# mux_usb.net
KiCad netlist of a schematic drawn in Altium Designer
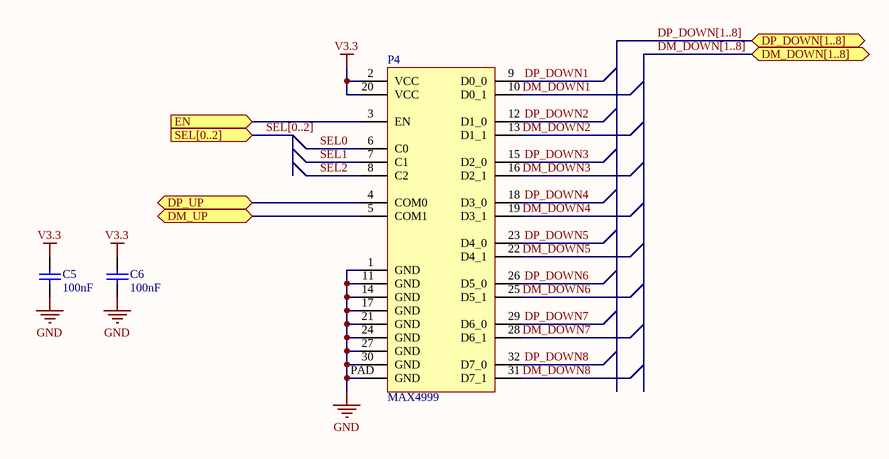
[diagram p0: mux_usb.SchDoc]

(export (version "E")
  (design (tool "Eeschema 10.0.6"))
  (components
    (comp (ref "C5") (value "100nF") (footprint "0402") (libsource (lib "misc") (part "Capacitor")))
    (comp (ref "C6") (value "100nF") (footprint "0402") (libsource (lib "misc") (part "Capacitor")))
    (comp (ref "P4") (value "MAX4999") (footprint "MAXIM_T3255+4") (libsource (lib "misc") (part "MAX4999")))
  )
  (nets
    (net (code "1") (name "/DM_DOWN1") (class "Default")
      (node (ref "P4") (pin "10") (pinfunction "D0_1_10") (pintype "passive"))
    )
    (net (code "2") (name "/DM_DOWN2") (class "Default")
      (node (ref "P4") (pin "13") (pinfunction "D1_1_13") (pintype "passive"))
    )
    (net (code "3") (name "/DM_DOWN3") (class "Default")
      (node (ref "P4") (pin "16") (pinfunction "D2_1_16") (pintype "passive"))
    )
    (net (code "4") (name "/DM_DOWN4") (class "Default")
      (node (ref "P4") (pin "19") (pinfunction "D3_1_19") (pintype "passive"))
    )
    (net (code "5") (name "/DM_DOWN5") (class "Default")
      (node (ref "P4") (pin "22") (pinfunction "D4_1_22") (pintype "passive"))
    )
    (net (code "6") (name "/DM_DOWN6") (class "Default")
      (node (ref "P4") (pin "25") (pinfunction "D5_1_25") (pintype "passive"))
    )
    (net (code "7") (name "/DM_DOWN7") (class "Default")
      (node (ref "P4") (pin "28") (pinfunction "D6_1_28") (pintype "passive"))
    )
    (net (code "8") (name "/DM_DOWN8") (class "Default")
      (node (ref "P4") (pin "31") (pinfunction "D7_1_31") (pintype "passive"))
    )
    (net (code "10") (name "/DM_UP") (class "Default")
      (node (ref "P4") (pin "5") (pinfunction "COM1_5") (pintype "passive"))
    )
    (net (code "11") (name "/DP_DOWN1") (class "Default")
      (node (ref "P4") (pin "9") (pinfunction "D0_0_9") (pintype "passive"))
    )
    (net (code "12") (name "/DP_DOWN2") (class "Default")
      (node (ref "P4") (pin "12") (pinfunction "D1_0_12") (pintype "passive"))
    )
    (net (code "13") (name "/DP_DOWN3") (class "Default")
      (node (ref "P4") (pin "15") (pinfunction "D2_0_15") (pintype "passive"))
    )
    (net (code "14") (name "/DP_DOWN4") (class "Default")
      (node (ref "P4") (pin "18") (pinfunction "D3_0_18") (pintype "passive"))
    )
    (net (code "15") (name "/DP_DOWN5") (class "Default")
      (node (ref "P4") (pin "23") (pinfunction "D4_0_23") (pintype "passive"))
    )
    (net (code "16") (name "/DP_DOWN6") (class "Default")
      (node (ref "P4") (pin "26") (pinfunction "D5_0_26") (pintype "passive"))
    )
    (net (code "17") (name "/DP_DOWN7") (class "Default")
      (node (ref "P4") (pin "29") (pinfunction "D6_0_29") (pintype "passive"))
    )
    (net (code "18") (name "/DP_DOWN8") (class "Default")
      (node (ref "P4") (pin "32") (pinfunction "D7_0_32") (pintype "passive"))
    )
    (net (code "20") (name "/DP_UP") (class "Default")
      (node (ref "P4") (pin "4") (pinfunction "COM0_4") (pintype "passive"))
    )
    (net (code "21") (name "/EN") (class "Default")
      (node (ref "P4") (pin "3") (pinfunction "EN_3") (pintype "passive"))
    )
    (net (code "22") (name "/SEL0") (class "Default")
      (node (ref "P4") (pin "6") (pinfunction "C0_6") (pintype "passive"))
    )
    (net (code "23") (name "/SEL1") (class "Default")
      (node (ref "P4") (pin "7") (pinfunction "C1_7") (pintype "passive"))
    )
    (net (code "24") (name "/SEL2") (class "Default")
      (node (ref "P4") (pin "8") (pinfunction "C2_8") (pintype "passive"))
    )
    (net (code "26") (name "GND") (class "Default")
      (node (ref "C5") (pin "1") (pinfunction "1_1") (pintype "passive"))
      (node (ref "C6") (pin "1") (pinfunction "1_1") (pintype "passive"))
      (node (ref "P4") (pin "1") (pinfunction "GND_1") (pintype "passive"))
      (node (ref "P4") (pin "11") (pinfunction "GND_11") (pintype "passive"))
      (node (ref "P4") (pin "14") (pinfunction "GND_14") (pintype "passive"))
      (node (ref "P4") (pin "17") (pinfunction "GND_17") (pintype "passive"))
      (node (ref "P4") (pin "21") (pinfunction "GND_21") (pintype "passive"))
      (node (ref "P4") (pin "24") (pinfunction "GND_24") (pintype "passive"))
      (node (ref "P4") (pin "27") (pinfunction "GND_27") (pintype "passive"))
      (node (ref "P4") (pin "30") (pinfunction "GND_30") (pintype "passive"))
      (node (ref "P4") (pin "PAD") (pinfunction "GND_PAD") (pintype "passive"))
    )
    (net (code "27") (name "V3.3") (class "Default")
      (node (ref "C5") (pin "2") (pinfunction "2_2") (pintype "passive"))
      (node (ref "C6") (pin "2") (pinfunction "2_2") (pintype "passive"))
      (node (ref "P4") (pin "2") (pinfunction "VCC_2") (pintype "passive"))
      (node (ref "P4") (pin "20") (pinfunction "VCC_20") (pintype "passive"))
    )
  )
)
